# 4001_4153_LO_V2.net
KiCad netlist of a schematic drawn in EAGLE
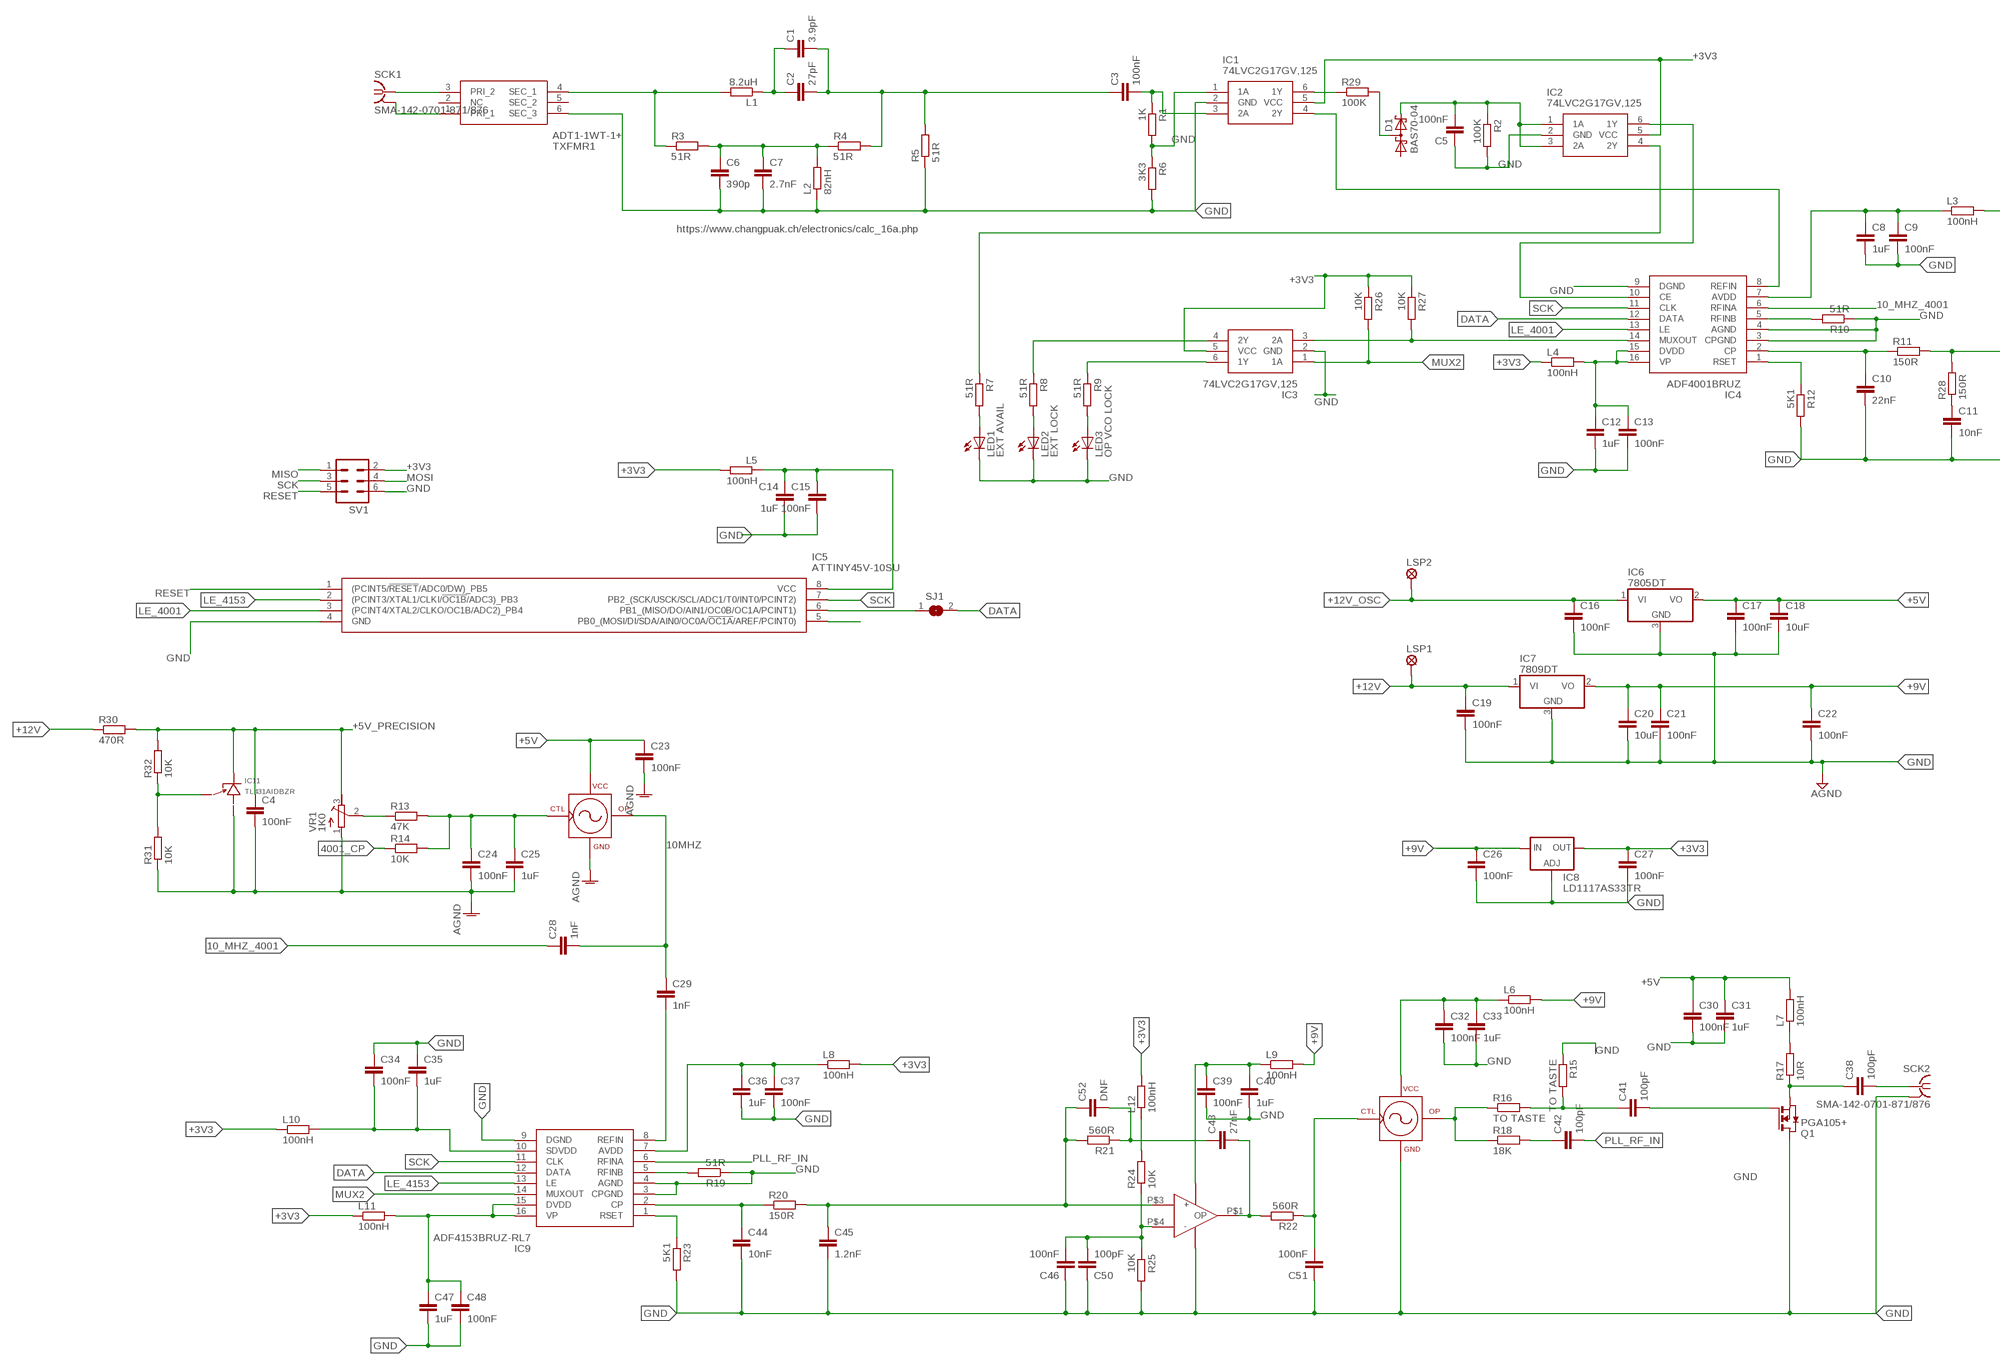
[diagram p0: schematic, sheet 1, part 1 of 2]
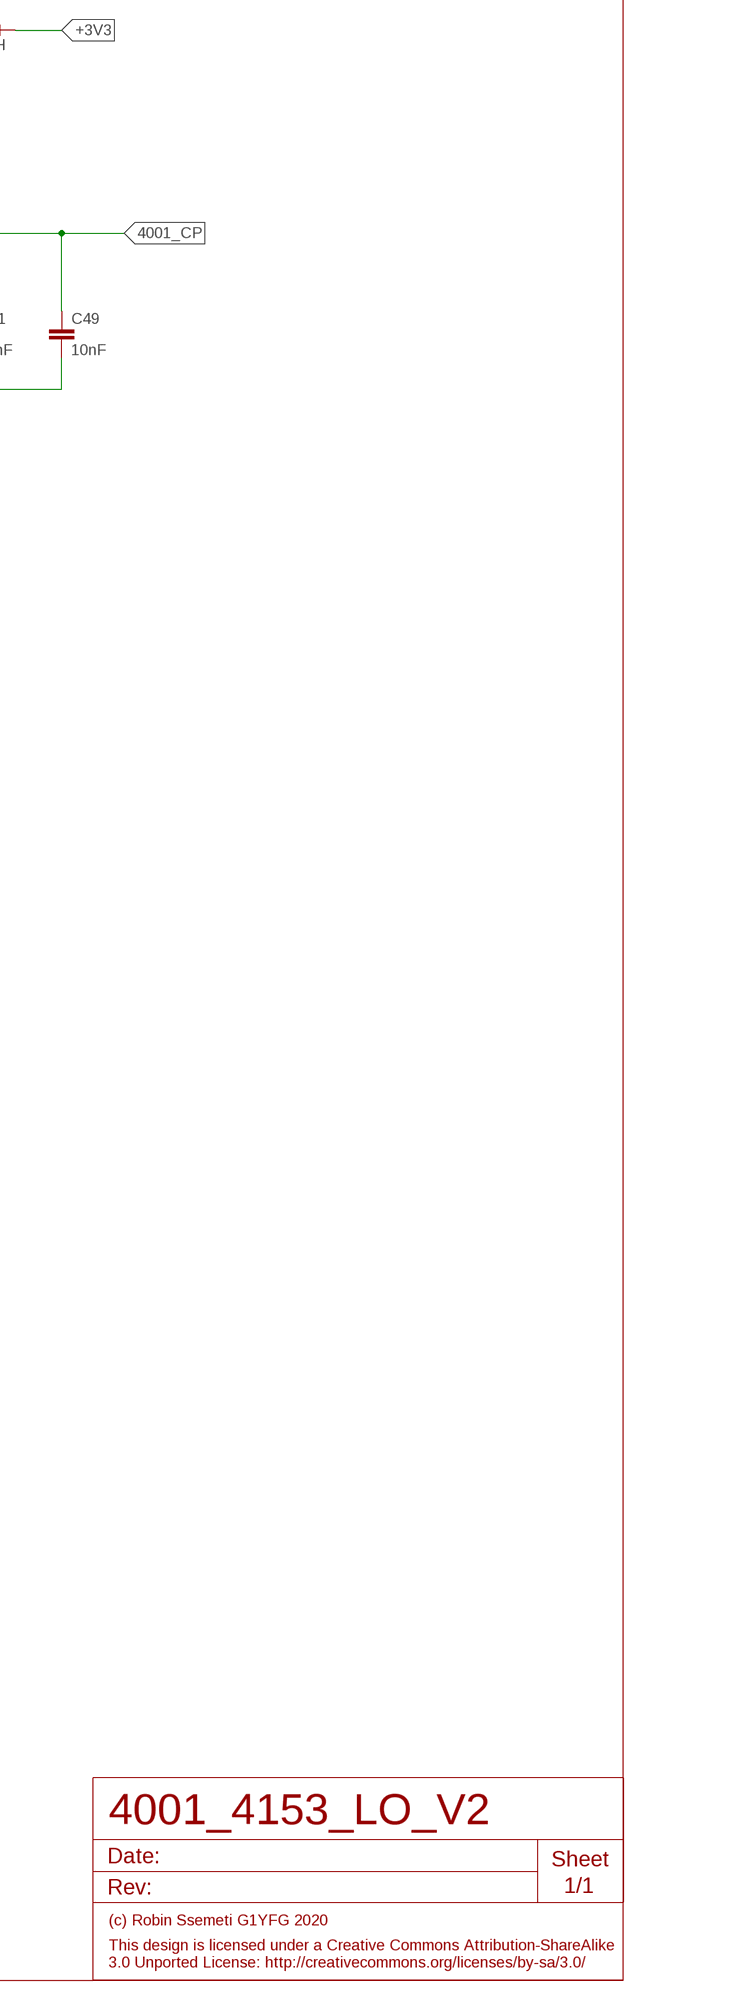
[diagram p1: schematic, sheet 1, part 2 of 2]

(export (version "E")
  (design (tool "Eeschema 10.0.6"))
  (components
    (comp (ref "C1")
      (value "3.9pF")
      (footprint "eagle-import:C0603")
      (libsource (lib "eagle-import") (part "resistor_C-EUC0603"))
    )
    (comp (ref "C2")
      (value "27pF")
      (footprint "eagle-import:C0603")
      (libsource (lib "eagle-import") (part "resistor_C-EUC0603"))
    )
    (comp (ref "C3")
      (value "100nF")
      (footprint "eagle-import:C0603")
      (libsource (lib "eagle-import") (part "resistor_C-EUC0603"))
    )
    (comp (ref "C4")
      (value "100nF")
      (footprint "eagle-import:C0603")
      (libsource (lib "eagle-import") (part "C-EUC0603"))
    )
    (comp (ref "C5")
      (value "100nF")
      (footprint "eagle-import:C0603")
      (libsource (lib "eagle-import") (part "resistor_C-EUC0603"))
    )
    (comp (ref "C6")
      (value "390p")
      (footprint "eagle-import:C0603")
      (libsource (lib "eagle-import") (part "resistor_C-EUC0603"))
    )
    (comp (ref "C7")
      (value "2.7nF")
      (footprint "eagle-import:C0603")
      (libsource (lib "eagle-import") (part "resistor_C-EUC0603"))
    )
    (comp (ref "C8")
      (value "1uF")
      (footprint "eagle-import:C0603")
      (libsource (lib "eagle-import") (part "resistor_C-EUC0603"))
    )
    (comp (ref "C9")
      (value "100nF")
      (footprint "eagle-import:C0603")
      (libsource (lib "eagle-import") (part "resistor_C-EUC0603"))
    )
    (comp (ref "C10")
      (value "22nF")
      (footprint "eagle-import:C0603")
      (libsource (lib "eagle-import") (part "resistor_C-EUC0603"))
    )
    (comp (ref "C11")
      (value "10nF")
      (footprint "eagle-import:C0603")
      (libsource (lib "eagle-import") (part "resistor_C-EUC0603"))
    )
    (comp (ref "C12")
      (value "1uF")
      (footprint "eagle-import:C0603")
      (libsource (lib "eagle-import") (part "resistor_C-EUC0603"))
    )
    (comp (ref "C13")
      (value "100nF")
      (footprint "eagle-import:C0603")
      (libsource (lib "eagle-import") (part "resistor_C-EUC0603"))
    )
    (comp (ref "C14")
      (value "1uF")
      (footprint "eagle-import:C0603")
      (libsource (lib "eagle-import") (part "resistor_C-EUC0603"))
    )
    (comp (ref "C15")
      (value "100nF")
      (footprint "eagle-import:C0603")
      (libsource (lib "eagle-import") (part "resistor_C-EUC0603"))
    )
    (comp (ref "C16")
      (value "100nF")
      (footprint "eagle-import:C0805")
      (libsource (lib "eagle-import") (part "C-EUC0805"))
    )
    (comp (ref "C17")
      (value "100nF")
      (footprint "eagle-import:C0805")
      (libsource (lib "eagle-import") (part "C-EUC0805"))
    )
    (comp (ref "C18")
      (value "10uF")
      (footprint "eagle-import:C0805")
      (libsource (lib "eagle-import") (part "C-EUC0805"))
    )
    (comp (ref "C19")
      (value "100nF")
      (footprint "eagle-import:C0805")
      (libsource (lib "eagle-import") (part "C-EUC0805"))
    )
    (comp (ref "C20")
      (value "10uF")
      (footprint "eagle-import:C0805")
      (libsource (lib "eagle-import") (part "C-EUC0805"))
    )
    (comp (ref "C21")
      (value "100nF")
      (footprint "eagle-import:C0805")
      (libsource (lib "eagle-import") (part "C-EUC0805"))
    )
    (comp (ref "C22")
      (value "100nF")
      (footprint "eagle-import:C0805")
      (libsource (lib "eagle-import") (part "C-EUC0805"))
    )
    (comp (ref "C23")
      (value "100nF")
      (footprint "eagle-import:C0603")
      (libsource (lib "eagle-import") (part "C-EUC0603"))
    )
    (comp (ref "C24")
      (value "100nF")
      (footprint "eagle-import:C0603")
      (libsource (lib "eagle-import") (part "C-EUC0603"))
    )
    (comp (ref "C25")
      (value "1uF")
      (footprint "eagle-import:C0603")
      (libsource (lib "eagle-import") (part "C-EUC0603"))
    )
    (comp (ref "C26")
      (value "100nF")
      (footprint "eagle-import:C0805")
      (libsource (lib "eagle-import") (part "C-EUC0805"))
    )
    (comp (ref "C27")
      (value "100nF")
      (footprint "eagle-import:C0805")
      (libsource (lib "eagle-import") (part "C-EUC0805"))
    )
    (comp (ref "C28")
      (value "1nF")
      (footprint "eagle-import:C0603")
      (libsource (lib "eagle-import") (part "resistor_C-EUC0603"))
    )
    (comp (ref "C29")
      (value "1nF")
      (footprint "eagle-import:C0603")
      (libsource (lib "eagle-import") (part "resistor_C-EUC0603"))
    )
    (comp (ref "C30")
      (value "100nF")
      (footprint "eagle-import:C0603")
      (libsource (lib "eagle-import") (part "resistor_C-EUC0603"))
    )
    (comp (ref "C31")
      (value "1uF")
      (footprint "eagle-import:C0603")
      (libsource (lib "eagle-import") (part "resistor_C-EUC0603"))
    )
    (comp (ref "C32")
      (value "100nF")
      (footprint "eagle-import:C0603")
      (libsource (lib "eagle-import") (part "resistor_C-EUC0603"))
    )
    (comp (ref "C33")
      (value "1uF")
      (footprint "eagle-import:C0603")
      (libsource (lib "eagle-import") (part "resistor_C-EUC0603"))
    )
    (comp (ref "C34")
      (value "100nF")
      (footprint "eagle-import:C0603")
      (libsource (lib "eagle-import") (part "resistor_C-EUC0603"))
    )
    (comp (ref "C35")
      (value "1uF")
      (footprint "eagle-import:C0603")
      (libsource (lib "eagle-import") (part "resistor_C-EUC0603"))
    )
    (comp (ref "C36")
      (value "1uF")
      (footprint "eagle-import:C0603")
      (libsource (lib "eagle-import") (part "resistor_C-EUC0603"))
    )
    (comp (ref "C37")
      (value "100nF")
      (footprint "eagle-import:C0603")
      (libsource (lib "eagle-import") (part "resistor_C-EUC0603"))
    )
    (comp (ref "C38")
      (value "100pF")
      (footprint "eagle-import:C0603")
      (libsource (lib "eagle-import") (part "resistor_C-EUC0603"))
    )
    (comp (ref "C39")
      (value "100nF")
      (footprint "eagle-import:C0603")
      (libsource (lib "eagle-import") (part "resistor_C-EUC0603"))
    )
    (comp (ref "C40")
      (value "1uF")
      (footprint "eagle-import:C0603")
      (libsource (lib "eagle-import") (part "resistor_C-EUC0603"))
    )
    (comp (ref "C41")
      (value "100pF")
      (footprint "eagle-import:C0603")
      (libsource (lib "eagle-import") (part "resistor_C-EUC0603"))
    )
    (comp (ref "C42")
      (value "100pF")
      (footprint "eagle-import:C0603")
      (libsource (lib "eagle-import") (part "resistor_C-EUC0603"))
    )
    (comp (ref "C43")
      (value "27nF")
      (footprint "eagle-import:C0603")
      (libsource (lib "eagle-import") (part "resistor_C-EUC0603"))
    )
    (comp (ref "C44")
      (value "10nF")
      (footprint "eagle-import:C0603")
      (libsource (lib "eagle-import") (part "resistor_C-EUC0603"))
    )
    (comp (ref "C45")
      (value "1.2nF")
      (footprint "eagle-import:C0603")
      (libsource (lib "eagle-import") (part "resistor_C-EUC0603"))
    )
    (comp (ref "C46")
      (value "100nF")
      (footprint "eagle-import:C0603")
      (libsource (lib "eagle-import") (part "resistor_C-EUC0603"))
    )
    (comp (ref "C47")
      (value "1uF")
      (footprint "eagle-import:C0603")
      (libsource (lib "eagle-import") (part "resistor_C-EUC0603"))
    )
    (comp (ref "C48")
      (value "100nF")
      (footprint "eagle-import:C0603")
      (libsource (lib "eagle-import") (part "resistor_C-EUC0603"))
    )
    (comp (ref "C49")
      (value "10nF")
      (footprint "eagle-import:C0603")
      (libsource (lib "eagle-import") (part "resistor_C-EUC0603"))
    )
    (comp (ref "C50")
      (value "100pF")
      (footprint "eagle-import:C0603")
      (libsource (lib "eagle-import") (part "resistor_C-EUC0603"))
    )
    (comp (ref "C51")
      (value "100nF")
      (footprint "eagle-import:C0603")
      (libsource (lib "eagle-import") (part "resistor_C-EUC0603"))
    )
    (comp (ref "C52")
      (value "DNF")
      (footprint "eagle-import:C0603")
      (libsource (lib "eagle-import") (part "resistor_C-EUC0603"))
    )
    (comp (ref "D1")
      (value "BAS70-04")
      (footprint "eagle-import:SOT23")
      (libsource (lib "eagle-import") (part "BAS70-04"))
    )
    (comp (ref "IC1")
      (value "74LVC2G17GV,125")
      (footprint "eagle-import:SOT95P275X110-6N")
      (fields (field (name "MOUSER_PART_NUMBER") "771-74LVC2G17GV-G"))
      (libsource (lib "eagle-import") (part "74LVC2G17GV,125"))
    )
    (comp (ref "IC2")
      (value "74LVC2G17GV,125")
      (footprint "eagle-import:SOT95P275X110-6N")
      (description "74LVC2G17 - Dual non-inverting Schmitt trigger with 5 V tolerant input@en-us")
      (fields
        (field (name "MOUSER_PART_NUMBER") "771-74LVC2G17GV-G")
        (field (name "ARROW_PART_NUMBER") "74LVC2G17GV,125")
        (field (name "ARROW_PRICE-STOCK") "https://www.arrow.com/en/products/74lvc2g17gv125/nexperia?region=nac")
        (field (name "HEIGHT") "1.1mm")
        (field (name "MANUFACTURER_NAME") "Nexperia")
        (field (name "MANUFACTURER_PART_NUMBER") "74LVC2G17GV,125")
        (field (name "MOUSER_PART_NUMBER_1") "771-74LVC2G17GV-G")
        (field (name "MOUSER_PRICE-STOCK") "https://www.mouser.co.uk/ProductDetail/Nexperia/74LVC2G17GV125?qs=me8TqzrmIYV0s3Bq3xwtOg%3D%3D")
      )
      (libsource (lib "eagle-import") (part "74LVC2G17GV,125"))
    )
    (comp (ref "IC3")
      (value "74LVC2G17GV,125")
      (footprint "eagle-import:SOT95P275X110-6N")
      (description "74LVC2G17 - Dual non-inverting Schmitt trigger with 5 V tolerant input@en-us")
      (fields
        (field (name "MOUSER_PART_NUMBER") "771-74LVC2G17GV-G")
        (field (name "ARROW_PART_NUMBER") "74LVC2G17GV,125")
        (field (name "ARROW_PRICE-STOCK") "https://www.arrow.com/en/products/74lvc2g17gv125/nexperia?region=nac")
        (field (name "HEIGHT") "1.1mm")
        (field (name "MANUFACTURER_NAME") "Nexperia")
        (field (name "MANUFACTURER_PART_NUMBER") "74LVC2G17GV,125")
        (field (name "MOUSER_PART_NUMBER_1") "771-74LVC2G17GV-G")
        (field (name "MOUSER_PRICE-STOCK") "https://www.mouser.co.uk/ProductDetail/Nexperia/74LVC2G17GV125?qs=me8TqzrmIYV0s3Bq3xwtOg%3D%3D")
      )
      (libsource (lib "eagle-import") (part "74LVC2G17GV,125"))
    )
    (comp (ref "IC4")
      (value "ADF4001BRUZ")
      (footprint "eagle-import:SOP65P640X120-16N")
      (fields (field (name "MOUSER_PART_NUMBER") "584-ADF4001BRUZ"))
      (libsource (lib "eagle-import") (part "ADF4001BRUZ"))
    )
    (comp (ref "IC5")
      (value "ATTINY45V-10SU")
      (footprint "eagle-import:SOIC127P798X216-8N")
      (fields (field (name "MOUSER_PART_NUMBER") "556-ATTINY45V10SU"))
      (libsource (lib "eagle-import") (part "ATTINY45V-10SU"))
    )
    (comp (ref "IC6")
      (value "7805DT")
      (footprint "eagle-import:TO252")
      (libsource (lib "eagle-import") (part "78DT05"))
    )
    (comp (ref "IC7")
      (value "7809DT")
      (footprint "eagle-import:TO252")
      (libsource (lib "eagle-import") (part "78DT05"))
    )
    (comp (ref "IC8")
      (value "LD1117AS33TR")
      (footprint "eagle-import:SOT223")
      (libsource (lib "eagle-import") (part "LD117A?STR"))
    )
    (comp (ref "IC9")
      (value "ADF4153BRUZ-RL7")
      (footprint "eagle-import:SOP65P640X120-16N")
      (fields (field (name "MOUSER_PART_NUMBER") "584-ADF4153BRUZ-R7"))
      (libsource (lib "eagle-import") (part "ADF4153BRUZ-RL7"))
    )
    (comp (ref "IC10")
      (value "MCP6H01T-E/LT")
      (footprint "eagle-import:SOT23-5")
      (fields (field (name "MPN") "MCP6H01T-E/LT "))
      (libsource (lib "eagle-import") (part "MCP6H01"))
    )
    (comp (ref "IC11")
      (value "TL431AIDBZR")
      (footprint "eagle-import:SOT23L")
      (libsource (lib "eagle-import") (part "TL431AIDBZR"))
    )
    (comp (ref "L1")
      (value "8.2uH")
      (footprint "eagle-import:R0603")
      (libsource (lib "eagle-import") (part "resistor_R-EU_R0603"))
    )
    (comp (ref "L2")
      (value "82nH")
      (footprint "eagle-import:R0603")
      (libsource (lib "eagle-import") (part "resistor_R-EU_R0603"))
    )
    (comp (ref "L3")
      (value "100nH")
      (footprint "eagle-import:R0603")
      (libsource (lib "eagle-import") (part "resistor_R-EU_R0603"))
    )
    (comp (ref "L4")
      (value "100nH")
      (footprint "eagle-import:R0603")
      (libsource (lib "eagle-import") (part "resistor_R-EU_R0603"))
    )
    (comp (ref "L5")
      (value "100nH")
      (footprint "eagle-import:R0603")
      (libsource (lib "eagle-import") (part "resistor_R-EU_R0603"))
    )
    (comp (ref "L6")
      (value "100nH")
      (footprint "eagle-import:R0603")
      (libsource (lib "eagle-import") (part "resistor_R-EU_R0603"))
    )
    (comp (ref "L7")
      (value "100nH")
      (footprint "eagle-import:R0603")
      (libsource (lib "eagle-import") (part "resistor_R-EU_R0603"))
    )
    (comp (ref "L8")
      (value "100nH")
      (footprint "eagle-import:R0603")
      (libsource (lib "eagle-import") (part "resistor_R-EU_R0603"))
    )
    (comp (ref "L9")
      (value "100nH")
      (footprint "eagle-import:R0603")
      (libsource (lib "eagle-import") (part "resistor_R-EU_R0603"))
    )
    (comp (ref "L10")
      (value "100nH")
      (footprint "eagle-import:R0603")
      (libsource (lib "eagle-import") (part "resistor_R-EU_R0603"))
    )
    (comp (ref "L11")
      (value "100nH")
      (footprint "eagle-import:R0603")
      (libsource (lib "eagle-import") (part "resistor_R-EU_R0603"))
    )
    (comp (ref "L12")
      (value "100nH")
      (footprint "eagle-import:R0603")
      (libsource (lib "eagle-import") (part "resistor_R-EU_R0603"))
    )
    (comp (ref "LED1")
      (value "EXT AVAIL")
      (footprint "eagle-import:LED3MM")
      (libsource (lib "eagle-import") (part "LED3MM"))
    )
    (comp (ref "LED2")
      (value "EXT LOCK")
      (footprint "eagle-import:LED3MM")
      (libsource (lib "eagle-import") (part "LED3MM"))
    )
    (comp (ref "LED3")
      (value "OP VCO LOCK")
      (footprint "eagle-import:LED3MM")
      (libsource (lib "eagle-import") (part "LED3MM"))
    )
    (comp (ref "LSP1")
      (value "LSP13")
      (footprint "eagle-import:LSP13")
      (libsource (lib "eagle-import") (part "LSP13"))
    )
    (comp (ref "LSP2")
      (value "LSP13")
      (footprint "eagle-import:LSP13")
      (libsource (lib "eagle-import") (part "LSP13"))
    )
    (comp (ref "OSC1")
      (value "CTI_OSC")
      (footprint "eagle-import:CTI_OSC")
      (libsource (lib "eagle-import") (part "CTI_OSC"))
    )
    (comp (ref "OSC2")
      (value "CRSYTELEK_127")
      (footprint "eagle-import:CRYSTEK_VCO")
      (libsource (lib "eagle-import") (part "CRSYTELEK_127"))
    )
    (comp (ref "Q1")
      (value "PGA105+")
      (footprint "eagle-import:SOT89")
      (libsource (lib "eagle-import") (part "NMOSSOT89"))
    )
    (comp (ref "R1")
      (value "1K")
      (footprint "eagle-import:R0603")
      (libsource (lib "eagle-import") (part "R-EU_R0603"))
    )
    (comp (ref "R2")
      (value "100K")
      (footprint "eagle-import:R0603")
      (libsource (lib "eagle-import") (part "R-EU_R0603"))
    )
    (comp (ref "R3")
      (value "51R")
      (footprint "eagle-import:R0603")
      (libsource (lib "eagle-import") (part "R-EU_R0603"))
    )
    (comp (ref "R4")
      (value "51R")
      (footprint "eagle-import:R0603")
      (libsource (lib "eagle-import") (part "R-EU_R0603"))
    )
    (comp (ref "R5")
      (value "51R")
      (footprint "eagle-import:R0603")
      (libsource (lib "eagle-import") (part "R-EU_R0603"))
    )
    (comp (ref "R6")
      (value "3K3")
      (footprint "eagle-import:R0603")
      (libsource (lib "eagle-import") (part "R-EU_R0603"))
    )
    (comp (ref "R7")
      (value "51R")
      (footprint "eagle-import:R0603")
      (libsource (lib "eagle-import") (part "R-EU_R0603"))
    )
    (comp (ref "R8")
      (value "51R")
      (footprint "eagle-import:R0603")
      (libsource (lib "eagle-import") (part "R-EU_R0603"))
    )
    (comp (ref "R9")
      (value "51R")
      (footprint "eagle-import:R0603")
      (libsource (lib "eagle-import") (part "R-EU_R0603"))
    )
    (comp (ref "R10")
      (value "51R")
      (footprint "eagle-import:R0603")
      (libsource (lib "eagle-import") (part "R-EU_R0603"))
    )
    (comp (ref "R11")
      (value "150R")
      (footprint "eagle-import:R0603")
      (libsource (lib "eagle-import") (part "R-EU_R0603"))
    )
    (comp (ref "R12")
      (value "5K1")
      (footprint "eagle-import:R0603")
      (libsource (lib "eagle-import") (part "R-EU_R0603"))
    )
    (comp (ref "R13")
      (value "47K")
      (footprint "eagle-import:R0603")
      (libsource (lib "eagle-import") (part "R-EU_R0603"))
    )
    (comp (ref "R14")
      (value "10K")
      (footprint "eagle-import:R0603")
      (libsource (lib "eagle-import") (part "R-EU_R0603"))
    )
    (comp (ref "R15")
      (value "TO TASTE")
      (footprint "eagle-import:R0603")
      (libsource (lib "eagle-import") (part "R-EU_R0603"))
    )
    (comp (ref "R16")
      (value "TO TASTE")
      (footprint "eagle-import:R0603")
      (libsource (lib "eagle-import") (part "R-EU_R0603"))
    )
    (comp (ref "R17")
      (value "10R")
      (footprint "eagle-import:R0603")
      (libsource (lib "eagle-import") (part "R-EU_R0603"))
    )
    (comp (ref "R18")
      (value "18K")
      (footprint "eagle-import:R0603")
      (libsource (lib "eagle-import") (part "R-EU_R0603"))
    )
    (comp (ref "R19")
      (value "51R")
      (footprint "eagle-import:R0603")
      (libsource (lib "eagle-import") (part "R-EU_R0603"))
    )
    (comp (ref "R20")
      (value "150R")
      (footprint "eagle-import:R0603")
      (libsource (lib "eagle-import") (part "R-EU_R0603"))
    )
    (comp (ref "R21")
      (value "560R")
      (footprint "eagle-import:R0603")
      (libsource (lib "eagle-import") (part "R-EU_R0603"))
    )
    (comp (ref "R22")
      (value "560R")
      (footprint "eagle-import:R0603")
      (libsource (lib "eagle-import") (part "R-EU_R0603"))
    )
    (comp (ref "R23")
      (value "5K1")
      (footprint "eagle-import:R0603")
      (libsource (lib "eagle-import") (part "R-EU_R0603"))
    )
    (comp (ref "R24")
      (value "10K")
      (footprint "eagle-import:R0603")
      (libsource (lib "eagle-import") (part "R-EU_R0603"))
    )
    (comp (ref "R25")
      (value "10K")
      (footprint "eagle-import:R0603")
      (libsource (lib "eagle-import") (part "R-EU_R0603"))
    )
    (comp (ref "R26")
      (value "10K")
      (footprint "eagle-import:R0603")
      (libsource (lib "eagle-import") (part "R-EU_R0603"))
    )
    (comp (ref "R27")
      (value "10K")
      (footprint "eagle-import:R0603")
      (libsource (lib "eagle-import") (part "R-EU_R0603"))
    )
    (comp (ref "R28")
      (value "150R")
      (footprint "eagle-import:R0603")
      (libsource (lib "eagle-import") (part "R-EU_R0603"))
    )
    (comp (ref "R29")
      (value "100K")
      (footprint "eagle-import:R0603")
      (libsource (lib "eagle-import") (part "R-EU_R0603"))
    )
    (comp (ref "R30")
      (value "470R")
      (footprint "eagle-import:R0603")
      (libsource (lib "eagle-import") (part "R-EU_R0603"))
    )
    (comp (ref "R31")
      (value "10K")
      (footprint "eagle-import:R0603")
      (libsource (lib "eagle-import") (part "R-EU_R0603"))
    )
    (comp (ref "R32")
      (value "10K")
      (footprint "eagle-import:R0603")
      (libsource (lib "eagle-import") (part "R-EU_R0603"))
    )
    (comp (ref "SCK1")
      (value "SMA-142-0701-871/876")
      (footprint "eagle-import:J502-ND-142-0701-871_876")
      (fields (field (name "MF") "JOHNSON COMPONENTS") (field (name "MPN") "142-0701-871"))
      (libsource (lib "eagle-import") (part "SMA-142-0701-871/876"))
    )
    (comp (ref "SCK2")
      (value "SMA-142-0701-871/876")
      (footprint "eagle-import:J502-ND-142-0701-871_876")
      (fields
        (field (name "MF") "JOHNSON COMPONENTS")
        (field (name "MPN") "142-0701-871")
        (field (name "MF_1") "JOHNSON COMPONENTS")
        (field (name "MPN_1") "142-0701-871")
        (field (name "OC_FARNELL") "1339835")
        (field (name "OC_NEWARK") "91B6105")
      )
      (libsource (lib "eagle-import") (part "SMA-142-0701-871/876"))
    )
    (comp (ref "SJ1") (value "SJ") (footprint "eagle-import:SJ") (libsource (lib "eagle-import") (part "SJ")))
    (comp (ref "SV1")
      (value "ML6")
      (footprint "eagle-import:ML6")
      (fields (field (name "MPN") "MC-254-06-00-ST-DIP ") (field (name "OC_FARNELL") "2843525"))
      (libsource (lib "eagle-import") (part "ML6"))
    )
    (comp (ref "TXFMR1")
      (value "ADT1-1WT-1+")
      (footprint "eagle-import:SOP254P691X284-6N")
      (fields (field (name "MOUSER_PART_NUMBER") "139-ADT1-1WT-1"))
      (libsource (lib "eagle-import") (part "ADT1-1WT-1+"))
    )
    (comp (ref "VR1")
      (value "1K0")
      (footprint "eagle-import:RTRIM64Y")
      (fields (field (name "MPN") "3296Y-1-103LF "))
      (libsource (lib "eagle-import") (part "R-TRIMM64Y"))
    )
  )
  (nets
    (net (code "1") (name "+3V3") (class "Default")
      (node (ref "C27") (pin "1") (pinfunction "1_1") (pintype "passive"))
      (node (ref "IC1") (pin "5") (pinfunction "VCC_5") (pintype "bidirectional"))
      (node (ref "IC2") (pin "5") (pinfunction "VCC_5") (pintype "bidirectional"))
      (node (ref "IC3") (pin "5") (pinfunction "VCC_5") (pintype "bidirectional"))
      (node (ref "IC8") (pin "4") (pinfunction "OUT_4") (pintype "passive"))
      (node (ref "L10") (pin "1") (pinfunction "1_1") (pintype "passive"))
      (node (ref "L11") (pin "1") (pinfunction "1_1") (pintype "passive"))
      (node (ref "L12") (pin "2") (pinfunction "2_2") (pintype "passive"))
      (node (ref "L3") (pin "2") (pinfunction "2_2") (pintype "passive"))
      (node (ref "L4") (pin "1") (pinfunction "1_1") (pintype "passive"))
      (node (ref "L5") (pin "2") (pinfunction "2_2") (pintype "passive"))
      (node (ref "L8") (pin "2") (pinfunction "2_2") (pintype "passive"))
      (node (ref "R26") (pin "1") (pinfunction "1_1") (pintype "passive"))
      (node (ref "R27") (pin "1") (pinfunction "1_1") (pintype "passive"))
      (node (ref "SV1") (pin "2") (pinfunction "2_2") (pintype "passive"))
    )
    (net (code "2") (name "+5V") (class "Default")
      (node (ref "C17") (pin "1") (pinfunction "1_1") (pintype "passive"))
      (node (ref "C18") (pin "1") (pinfunction "1_1") (pintype "passive"))
      (node (ref "C23") (pin "1") (pinfunction "1_1") (pintype "passive"))
      (node (ref "C30") (pin "1") (pinfunction "1_1") (pintype "passive"))
      (node (ref "C31") (pin "1") (pinfunction "1_1") (pintype "passive"))
      (node (ref "IC6") (pin "2") (pinfunction "VO_2") (pintype "passive"))
      (node (ref "L7") (pin "2") (pinfunction "2_2") (pintype "passive"))
      (node (ref "OSC1") (pin "VCC") (pinfunction "VCC_VCC") (pintype "bidirectional"))
    )
    (net (code "3") (name "+9V") (class "Default")
      (node (ref "C20") (pin "1") (pinfunction "1_1") (pintype "passive"))
      (node (ref "C21") (pin "1") (pinfunction "1_1") (pintype "passive"))
      (node (ref "C22") (pin "1") (pinfunction "1_1") (pintype "passive"))
      (node (ref "C26") (pin "1") (pinfunction "1_1") (pintype "passive"))
      (node (ref "IC7") (pin "2") (pinfunction "VO_2") (pintype "passive"))
      (node (ref "IC8") (pin "3") (pinfunction "IN_3") (pintype "input"))
      (node (ref "L6") (pin "2") (pinfunction "2_2") (pintype "passive"))
      (node (ref "L9") (pin "2") (pinfunction "2_2") (pintype "passive"))
    )
    (net (code "4") (name "+12V") (class "Default")
      (node (ref "C19") (pin "1") (pinfunction "1_1") (pintype "passive"))
      (node (ref "IC7") (pin "1") (pinfunction "VI_1") (pintype "input"))
      (node (ref "LSP1") (pin "MP") (pinfunction "MP_MP") (pintype "passive"))
      (node (ref "R30") (pin "1") (pinfunction "1_1") (pintype "passive"))
    )
    (net (code "5") (name "+12V_OSC") (class "Default")
      (node (ref "C16") (pin "1") (pinfunction "1_1") (pintype "passive"))
      (node (ref "IC6") (pin "1") (pinfunction "VI_1") (pintype "input"))
      (node (ref "LSP2") (pin "MP") (pinfunction "MP_MP") (pintype "passive"))
    )
    (net (code "6") (name "/+5V_PRECISION") (class "Default")
      (node (ref "C4") (pin "1") (pinfunction "1_1") (pintype "passive"))
      (node (ref "IC11") (pin "G") (pinfunction "CATHODE_G") (pintype "bidirectional"))
      (node (ref "R30") (pin "2") (pinfunction "2_2") (pintype "passive"))
      (node (ref "R32") (pin "2") (pinfunction "2_2") (pintype "passive"))
      (node (ref "VR1") (pin "3") (pinfunction "A_3") (pintype "passive"))
    )
    (net (code "7") (name "/10MHZ") (class "Default")
      (node (ref "C28") (pin "2") (pinfunction "2_2") (pintype "passive"))
      (node (ref "C29") (pin "1") (pinfunction "1_1") (pintype "passive"))
      (node (ref "OSC1") (pin "OUT") (pinfunction "OP_OUT") (pintype "bidirectional"))
    )
    (net (code "8") (name "/MISO") (class "Default")
      (node (ref "IC5") (pin "6") (pinfunction "PB1_(MISO/DO/AIN1/OC0B/OC1A/PCINT1)_6") (pintype "bidirectional"))
      (node (ref "SJ1") (pin "1") (pinfunction "1_1") (pintype "passive"))
      (node (ref "SV1") (pin "1") (pinfunction "1_1") (pintype "passive"))
    )
    (net (code "9") (name "/MOSI") (class "Default")
      (node (ref "IC5") (pin "5") (pinfunction "PB0_(MOSI/DI/SDA/AIN0/OC0A/~{OC1A}/AREF/PCINT0)_5") (pintype "bidirectional"))
      (node (ref "SV1") (pin "4") (pinfunction "4_4") (pintype "passive"))
    )
    (net (code "10") (name "/RESET") (class "Default")
      (node (ref "IC5") (pin "1") (pinfunction "(PCINT5/~{RESET}/ADC0/DW)_PB5_1") (pintype "bidirectional"))
      (node (ref "SV1") (pin "5") (pinfunction "5_5") (pintype "passive"))
    )
    (net (code "11") (name "10_MHZ_4001") (class "Default")
      (node (ref "C28") (pin "1") (pinfunction "1_1") (pintype "passive"))
      (node (ref "IC4") (pin "6") (pinfunction "RFINA_6") (pintype "bidirectional"))
    )
    (net (code "12") (name "4001_CP") (class "Default")
      (node (ref "C49") (pin "1") (pinfunction "1_1") (pintype "passive"))
      (node (ref "R11") (pin "2") (pinfunction "2_2") (pintype "passive"))
      (node (ref "R14") (pin "1") (pinfunction "1_1") (pintype "passive"))
      (node (ref "R28") (pin "2") (pinfunction "2_2") (pintype "passive"))
    )
    (net (code "13") (name "DATA") (class "Default")
      (node (ref "IC4") (pin "12") (pinfunction "DATA_12") (pintype "bidirectional"))
      (node (ref "IC9") (pin "12") (pinfunction "DATA_12") (pintype "bidirectional"))
      (node (ref "SJ1") (pin "2") (pinfunction "2_2") (pintype "passive"))
    )
    (net (code "14") (name "GND") (class "Default")
      (node (ref "C10") (pin "2") (pinfunction "2_2") (pintype "passive"))
      (node (ref "C11") (pin "2") (pinfunction "2_2") (pintype "passive"))
      (node (ref "C12") (pin "2") (pinfunction "2_2") (pintype "passive"))
      (node (ref "C13") (pin "2") (pinfunction "2_2") (pintype "passive"))
      (node (ref "C14") (pin "2") (pinfunction "2_2") (pintype "passive"))
      (node (ref "C15") (pin "2") (pinfunction "2_2") (pintype "passive"))
      (node (ref "C16") (pin "2") (pinfunction "2_2") (pintype "passive"))
      (node (ref "C17") (pin "2") (pinfunction "2_2") (pintype "passive"))
      (node (ref "C18") (pin "2") (pinfunction "2_2") (pintype "passive"))
      (node (ref "C19") (pin "2") (pinfunction "2_2") (pintype "passive"))
      (node (ref "C20") (pin "2") (pinfunction "2_2") (pintype "passive"))
      (node (ref "C21") (pin "2") (pinfunction "2_2") (pintype "passive"))
      (node (ref "C22") (pin "2") (pinfunction "2_2") (pintype "passive"))
      (node (ref "C23") (pin "2") (pinfunction "2_2") (pintype "passive"))
      (node (ref "C24") (pin "2") (pinfunction "2_2") (pintype "passive"))
      (node (ref "C25") (pin "2") (pinfunction "2_2") (pintype "passive"))
      (node (ref "C26") (pin "2") (pinfunction "2_2") (pintype "passive"))
      (node (ref "C27") (pin "2") (pinfunction "2_2") (pintype "passive"))
      (node (ref "C30") (pin "2") (pinfunction "2_2") (pintype "passive"))
      (node (ref "C31") (pin "2") (pinfunction "2_2") (pintype "passive"))
      (node (ref "C32") (pin "2") (pinfunction "2_2") (pintype "passive"))
      (node (ref "C33") (pin "2") (pinfunction "2_2") (pintype "passive"))
      (node (ref "C34") (pin "1") (pinfunction "1_1") (pintype "passive"))
      (node (ref "C35") (pin "1") (pinfunction "1_1") (pintype "passive"))
      (node (ref "C36") (pin "2") (pinfunction "2_2") (pintype "passive"))
      (node (ref "C37") (pin "2") (pinfunction "2_2") (pintype "passive"))
      (node (ref "C39") (pin "2") (pinfunction "2_2") (pintype "passive"))
      (node (ref "C4") (pin "2") (pinfunction "2_2") (pintype "passive"))
      (node (ref "C40") (pin "2") (pinfunction "2_2") (pintype "passive"))
      (node (ref "C44") (pin "2") (pinfunction "2_2") (pintype "passive"))
      (node (ref "C45") (pin "2") (pinfunction "2_2") (pintype "passive"))
      (node (ref "C46") (pin "1") (pinfunction "1_1") (pintype "passive"))
      (node (ref "C47") (pin "2") (pinfunction "2_2") (pintype "passive"))
      (node (ref "C48") (pin "2") (pinfunction "2_2") (pintype "passive"))
      (node (ref "C49") (pin "2") (pinfunction "2_2") (pintype "passive"))
      (node (ref "C5") (pin "1") (pinfunction "1_1") (pintype "passive"))
      (node (ref "C50") (pin "1") (pinfunction "1_1") (pintype "passive"))
      (node (ref "C51") (pin "1") (pinfunction "1_1") (pintype "passive"))
      (node (ref "C6") (pin "2") (pinfunction "2_2") (pintype "passive"))
      (node (ref "C7") (pin "2") (pinfunction "2_2") (pintype "passive"))
      (node (ref "C8") (pin "2") (pinfunction "2_2") (pintype "passive"))
      (node (ref "C9") (pin "2") (pinfunction "2_2") (pintype "passive"))
      (node (ref "IC1") (pin "2") (pinfunction "GND_2") (pintype "bidirectional"))
      (node (ref "IC10") (pin "P$2") (pinfunction "-VE_P$2") (pintype "bidirectional"))
      (node (ref "IC11") (pin "D") (pinfunction "ANODE_D") (pintype "bidirectional"))
      (node (ref "IC2") (pin "2") (pinfunction "GND_2") (pintype "bidirectional"))
      (node (ref "IC3") (pin "2") (pinfunction "GND_2") (pintype "bidirectional"))
      (node (ref "IC4") (pin "3") (pinfunction "CPGND_3") (pintype "bidirectional"))
      (node (ref "IC4") (pin "4") (pinfunction "AGND_4") (pintype "bidirectional"))
      (node (ref "IC4") (pin "9") (pinfunction "DGND_9") (pintype "bidirectional"))
      (node (ref "IC5") (pin "4") (pinfunction "GND_4") (pintype "bidirectional"))
      (node (ref "IC6") (pin "3") (pinfunction "GND_3") (pintype "passive"))
      (node (ref "IC7") (pin "3") (pinfunction "GND_3") (pintype "passive"))
      (node (ref "IC8") (pin "1") (pinfunction "ADJ_1") (pintype "input"))
      (node (ref "IC9") (pin "3") (pinfunction "CPGND_3") (pintype "bidirectional"))
      (node (ref "IC9") (pin "4") (pinfunction "AGND_4") (pintype "bidirectional"))
      (node (ref "IC9") (pin "9") (pinfunction "DGND_9") (pintype "bidirectional"))
      (node (ref "L2") (pin "1") (pinfunction "1_1") (pintype "passive"))
      (node (ref "LED1") (pin "K") (pinfunction "C_K") (pintype "passive"))
      (node (ref "LED2") (pin "K") (pinfunction "C_K") (pintype "passive"))
      (node (ref "LED3") (pin "K") (pinfunction "C_K") (pintype "passive"))
      (node (ref "OSC1") (pin "GND") (pinfunction "GND_GND") (pintype "bidirectional"))
      (node (ref "OSC2") (pin "P$1") (pinfunction "GND_P$1") (pintype "bidirectional"))
      (node (ref "OSC2") (pin "P$11") (pinfunction "GND_P$11") (pintype "bidirectional"))
      (node (ref "OSC2") (pin "P$12") (pinfunction "GND_P$12") (pintype "bidirectional"))
      (node (ref "OSC2") (pin "P$13") (pinfunction "GND_P$13") (pintype "bidirectional"))
      (node (ref "OSC2") (pin "P$15") (pinfunction "GND_P$15") (pintype "bidirectional"))
      (node (ref "OSC2") (pin "P$16") (pinfunction "GND_P$16") (pintype "bidirectional"))
      (node (ref "OSC2") (pin "P$3") (pinfunction "GND_P$3") (pintype "bidirectional"))
      (node (ref "OSC2") (pin "P$4") (pinfunction "GND_P$4") (pintype "bidirectional"))
      (node (ref "OSC2") (pin "P$5") (pinfunction "GND_P$5") (pintype "bidirectional"))
      (node (ref "OSC2") (pin "P$6") (pinfunction "GND_P$6") (pintype "bidirectional"))
      (node (ref "OSC2") (pin "P$7") (pinfunction "GND_P$7") (pintype "bidirectional"))
      (node (ref "OSC2") (pin "P$8") (pinfunction "GND_P$8") (pintype "bidirectional"))
      (node (ref "OSC2") (pin "P$9") (pinfunction "GND_P$9") (pintype "bidirectional"))
      (node (ref "Q1") (pin "2") (pinfunction "D_2") (pintype "passive"))
      (node (ref "R10") (pin "1") (pinfunction "1_1") (pintype "passive"))
      (node (ref "R12") (pin "2") (pinfunction "2_2") (pintype "passive"))
      (node (ref "R15") (pin "1") (pinfunction "1_1") (pintype "passive"))
      (node (ref "R19") (pin "1") (pinfunction "1_1") (pintype "passive"))
      (node (ref "R2") (pin "2") (pinfunction "2_2") (pintype "passive"))
      (node (ref "R23") (pin "2") (pinfunction "2_2") (pintype "passive"))
      (node (ref "R25") (pin "2") (pinfunction "2_2") (pintype "passive"))
      (node (ref "R31") (pin "1") (pinfunction "1_1") (pintype "passive"))
      (node (ref "R5") (pin "1") (pinfunction "1_1") (pintype "passive"))
      (node (ref "R6") (pin "2") (pinfunction "2_2") (pintype "passive"))
      (node (ref "SCK1") (pin "G@1") (pinfunction "GND_G@1") (pintype "power_in"))
      (node (ref "SCK2") (pin "G@1") (pinfunction "GND_G@1") (pintype "power_in"))
      (node (ref "SV1") (pin "6") (pinfunction "6_6") (pintype "passive"))
      (node (ref "TXFMR1") (pin "1") (pinfunction "PRI_1_1") (pintype "bidirectional"))
      (node (ref "TXFMR1") (pin "6") (pinfunction "SEC_3_6") (pintype "bidirectional"))
      (node (ref "VR1") (pin "1") (pinfunction "E_1") (pintype "passive"))
    )
    (net (code "15") (name "LE_4001") (class "Default")
      (node (ref "IC4") (pin "13") (pinfunction "LE_13") (pintype "bidirectional"))
      (node (ref "IC5") (pin "3") (pinfunction "(PCINT4/XTAL2/CLKO/OC1B/ADC2)_PB4_3") (pintype "bidirectional"))
    )
    (net (code "16") (name "LE_4153") (class "Default")
      (node (ref "IC5") (pin "2") (pinfunction "(PCINT3/XTAL1/CLKI/~{OC1B}/ADC3)_PB3_2") (pintype "bidirectional"))
      (node (ref "IC9") (pin "13") (pinfunction "LE_13") (pintype "bidirectional"))
    )
    (net (code "17") (name "MUX2") (class "Default")
      (node (ref "IC3") (pin "1") (pinfunction "1A_1") (pintype "bidirectional"))
      (node (ref "IC9") (pin "14") (pinfunction "MUXOUT_14") (pintype "bidirectional"))
      (node (ref "R26") (pin "2") (pinfunction "2_2") (pintype "passive"))
    )
    (net (code "18") (name "Net-(C1-Pad1)") (class "Default")
      (node (ref "C1") (pin "1") (pinfunction "1_1") (pintype "passive"))
      (node (ref "C2") (pin "1") (pinfunction "1_1") (pintype "passive"))
      (node (ref "L1") (pin "1") (pinfunction "1_1") (pintype "passive"))
    )
    (net (code "19") (name "Net-(C1-Pad2)") (class "Default")
      (node (ref "C1") (pin "2") (pinfunction "2_2") (pintype "passive"))
      (node (ref "C2") (pin "2") (pinfunction "2_2") (pintype "passive"))
      (node (ref "C3") (pin "1") (pinfunction "1_1") (pintype "passive"))
      (node (ref "R4") (pin "2") (pinfunction "2_2") (pintype "passive"))
      (node (ref "R5") (pin "2") (pinfunction "2_2") (pintype "passive"))
    )
    (net (code "20") (name "Net-(C6-Pad1)") (class "Default")
      (node (ref "C6") (pin "1") (pinfunction "1_1") (pintype "passive"))
      (node (ref "C7") (pin "1") (pinfunction "1_1") (pintype "passive"))
      (node (ref "L2") (pin "2") (pinfunction "2_2") (pintype "passive"))
      (node (ref "R3") (pin "2") (pinfunction "2_2") (pintype "passive"))
      (node (ref "R4") (pin "1") (pinfunction "1_1") (pintype "passive"))
    )
    (net (code "21") (name "Net-(C11-Pad1)") (class "Default")
      (node (ref "C11") (pin "1") (pinfunction "1_1") (pintype "passive"))
      (node (ref "R28") (pin "1") (pinfunction "1_1") (pintype "passive"))
    )
    (net (code "22") (name "Net-(C38-Pad2)") (class "Default")
      (node (ref "C38") (pin "2") (pinfunction "2_2") (pintype "passive"))
      (node (ref "SCK2") (pin "1") (pinfunction "1_1") (pintype "passive"))
    )
    (net (code "23") (name "Net-(C41-Pad1)") (class "Default")
      (node (ref "C41") (pin "1") (pinfunction "1_1") (pintype "passive"))
      (node (ref "R15") (pin "2") (pinfunction "2_2") (pintype "passive"))
      (node (ref "R16") (pin "2") (pinfunction "2_2") (pintype "passive"))
    )
    (net (code "24") (name "Net-(C42-Pad1)") (class "Default")
      (node (ref "C42") (pin "1") (pinfunction "1_1") (pintype "passive"))
      (node (ref "R18") (pin "2") (pinfunction "2_2") (pintype "passive"))
    )
    (net (code "25") (name "Net-(C43-Pad1)") (class "Default")
      (node (ref "C43") (pin "1") (pinfunction "1_1") (pintype "passive"))
      (node (ref "C52") (pin "2") (pinfunction "2_2") (pintype "passive"))
      (node (ref "R21") (pin "1") (pinfunction "1_1") (pintype "passive"))
    )
    (net (code "26") (name "Net-(D1-C1A2)") (class "Default")
      (node (ref "D1") (pin "3") (pinfunction "C1A2_3") (pintype "passive"))
      (node (ref "R29") (pin "2") (pinfunction "2_2") (pintype "passive"))
    )
    (net (code "27") (name "Net-(D1-C2)") (class "Default")
      (node (ref "C5") (pin "2") (pinfunction "2_2") (pintype "passive"))
      (node (ref "D1") (pin "2") (pinfunction "C2_2") (pintype "passive"))
      (node (ref "IC2") (pin "1") (pinfunction "1A_1") (pintype "bidirectional"))
      (node (ref "IC2") (pin "3") (pinfunction "2A_3") (pintype "bidirectional"))
      (node (ref "R2") (pin "1") (pinfunction "1_1") (pintype "passive"))
    )
    (net (code "28") (name "Net-(IC1-1A)") (class "Default")
      (node (ref "IC1") (pin "1") (pinfunction "1A_1") (pintype "bidirectional"))
      (node (ref "R1") (pin "2") (pinfunction "2_2") (pintype "passive"))
      (node (ref "R6") (pin "1") (pinfunction "1_1") (pintype "passive"))
    )
    (net (code "29") (name "Net-(IC1-1Y)") (class "Default")
      (node (ref "IC1") (pin "6") (pinfunction "1Y_6") (pintype "bidirectional"))
      (node (ref "R29") (pin "1") (pinfunction "1_1") (pintype "passive"))
    )
    (net (code "30") (name "Net-(IC1-2A)") (class "Default")
      (node (ref "C3") (pin "2") (pinfunction "2_2") (pintype "passive"))
      (node (ref "IC1") (pin "3") (pinfunction "2A_3") (pintype "bidirectional"))
      (node (ref "R1") (pin "1") (pinfunction "1_1") (pintype "passive"))
    )
    (net (code "31") (name "Net-(IC1-2Y)") (class "Default")
      (node (ref "IC1") (pin "4") (pinfunction "2Y_4") (pintype "bidirectional"))
      (node (ref "IC4") (pin "8") (pinfunction "REFIN_8") (pintype "bidirectional"))
    )
    (net (code "32") (name "Net-(IC2-1Y)") (class "Default")
      (node (ref "IC2") (pin "6") (pinfunction "1Y_6") (pintype "bidirectional"))
      (node (ref "IC4") (pin "10") (pinfunction "CE_10") (pintype "bidirectional"))
    )
    (net (code "33") (name "Net-(IC2-2Y)") (class "Default")
      (node (ref "IC2") (pin "4") (pinfunction "2Y_4") (pintype "bidirectional"))
      (node (ref "R7") (pin "1") (pinfunction "1_1") (pintype "passive"))
    )
    (net (code "34") (name "Net-(IC3-1Y)") (class "Default")
      (node (ref "IC3") (pin "6") (pinfunction "1Y_6") (pintype "bidirectional"))
      (node (ref "R9") (pin "1") (pinfunction "1_1") (pintype "passive"))
    )
    (net (code "35") (name "Net-(IC3-2A)") (class "Default")
      (node (ref "IC3") (pin "3") (pinfunction "2A_3") (pintype "bidirectional"))
      (node (ref "IC4") (pin "14") (pinfunction "MUXOUT_14") (pintype "bidirectional"))
      (node (ref "R27") (pin "2") (pinfunction "2_2") (pintype "passive"))
    )
    (net (code "36") (name "Net-(IC3-2Y)") (class "Default")
      (node (ref "IC3") (pin "4") (pinfunction "2Y_4") (pintype "bidirectional"))
      (node (ref "R8") (pin "1") (pinfunction "1_1") (pintype "passive"))
    )
    (net (code "37") (name "Net-(IC4-AVDD)") (class "Default")
      (node (ref "C8") (pin "1") (pinfunction "1_1") (pintype "passive"))
      (node (ref "C9") (pin "1") (pinfunction "1_1") (pintype "passive"))
      (node (ref "IC4") (pin "7") (pinfunction "AVDD_7") (pintype "bidirectional"))
      (node (ref "L3") (pin "1") (pinfunction "1_1") (pintype "passive"))
    )
    (net (code "38") (name "Net-(IC4-CP)") (class "Default")
      (node (ref "C10") (pin "1") (pinfunction "1_1") (pintype "passive"))
      (node (ref "IC4") (pin "2") (pinfunction "CP_2") (pintype "bidirectional"))
      (node (ref "R11") (pin "1") (pinfunction "1_1") (pintype "passive"))
    )
    (net (code "39") (name "Net-(IC4-DVDD)") (class "Default")
      (node (ref "C12") (pin "1") (pinfunction "1_1") (pintype "passive"))
      (node (ref "C13") (pin "1") (pinfunction "1_1") (pintype "passive"))
      (node (ref "IC4") (pin "15") (pinfunction "DVDD_15") (pintype "bidirectional"))
      (node (ref "IC4") (pin "16") (pinfunction "VP_16") (pintype "bidirectional"))
      (node (ref "L4") (pin "2") (pinfunction "2_2") (pintype "passive"))
    )
    (net (code "40") (name "Net-(IC4-RFINB)") (class "Default")
      (node (ref "IC4") (pin "5") (pinfunction "RFINB_5") (pintype "bidirectional"))
      (node (ref "R10") (pin "2") (pinfunction "2_2") (pintype "passive"))
    )
    (net (code "41") (name "Net-(IC4-RSET)") (class "Default")
      (node (ref "IC4") (pin "1") (pinfunction "RSET_1") (pintype "bidirectional"))
      (node (ref "R12") (pin "1") (pinfunction "1_1") (pintype "passive"))
    )
    (net (code "42") (name "Net-(IC5-VCC)") (class "Default")
      (node (ref "C14") (pin "1") (pinfunction "1_1") (pintype "passive"))
      (node (ref "C15") (pin "1") (pinfunction "1_1") (pintype "passive"))
      (node (ref "IC5") (pin "8") (pinfunction "VCC_8") (pintype "bidirectional"))
      (node (ref "L5") (pin "1") (pinfunction "1_1") (pintype "passive"))
    )
    (net (code "43") (name "Net-(IC9-AVDD)") (class "Default")
      (node (ref "C36") (pin "1") (pinfunction "1_1") (pintype "passive"))
      (node (ref "C37") (pin "1") (pinfunction "1_1") (pintype "passive"))
      (node (ref "IC9") (pin "7") (pinfunction "AVDD_7") (pintype "bidirectional"))
      (node (ref "L8") (pin "1") (pinfunction "1_1") (pintype "passive"))
    )
    (net (code "44") (name "Net-(IC9-CP)") (class "Default")
      (node (ref "C44") (pin "1") (pinfunction "1_1") (pintype "passive"))
      (node (ref "IC9") (pin "2") (pinfunction "CP_2") (pintype "bidirectional"))
      (node (ref "R20") (pin "1") (pinfunction "1_1") (pintype "passive"))
    )
    (net (code "45") (name "Net-(IC9-DVDD)") (class "Default")
      (node (ref "C47") (pin "1") (pinfunction "1_1") (pintype "passive"))
      (node (ref "C48") (pin "1") (pinfunction "1_1") (pintype "passive"))
      (node (ref "IC9") (pin "15") (pinfunction "DVDD_15") (pintype "bidirectional"))
      (node (ref "IC9") (pin "16") (pinfunction "VP_16") (pintype "bidirectional"))
      (node (ref "L11") (pin "2") (pinfunction "2_2") (pintype "passive"))
    )
    (net (code "46") (name "Net-(IC9-REFIN)") (class "Default")
      (node (ref "C29") (pin "2") (pinfunction "2_2") (pintype "passive"))
      (node (ref "IC9") (pin "8") (pinfunction "REFIN_8") (pintype "bidirectional"))
    )
    (net (code "47") (name "Net-(IC9-RFINB)") (class "Default")
      (node (ref "IC9") (pin "5") (pinfunction "RFINB_5") (pintype "bidirectional"))
      (node (ref "R19") (pin "2") (pinfunction "2_2") (pintype "passive"))
    )
    (net (code "48") (name "Net-(IC9-RSET)") (class "Default")
      (node (ref "IC9") (pin "1") (pinfunction "RSET_1") (pintype "bidirectional"))
      (node (ref "R23") (pin "1") (pinfunction "1_1") (pintype "passive"))
    )
    (net (code "49") (name "Net-(IC9-SDVDD)") (class "Default")
      (node (ref "C34") (pin "2") (pinfunction "2_2") (pintype "passive"))
      (node (ref "C35") (pin "2") (pinfunction "2_2") (pintype "passive"))
      (node (ref "IC9") (pin "10") (pinfunction "SDVDD_10") (pintype "bidirectional"))
      (node (ref "L10") (pin "2") (pinfunction "2_2") (pintype "passive"))
    )
    (net (code "50") (name "Net-(IC10-+)") (class "Default")
      (node (ref "C45") (pin "1") (pinfunction "1_1") (pintype "passive"))
      (node (ref "C52") (pin "1") (pinfunction "1_1") (pintype "passive"))
      (node (ref "IC10") (pin "P$3") (pinfunction "+_P$3") (pintype "bidirectional"))
      (node (ref "R20") (pin "2") (pinfunction "2_2") (pintype "passive"))
      (node (ref "R21") (pin "2") (pinfunction "2_2") (pintype "passive"))
    )
    (net (code "51") (name "Net-(IC10-+VE)") (class "Default")
      (node (ref "C39") (pin "1") (pinfunction "1_1") (pintype "passive"))
      (node (ref "C40") (pin "1") (pinfunction "1_1") (pintype "passive"))
      (node (ref "IC10") (pin "P$6") (pinfunction "+VE_P$6") (pintype "bidirectional"))
      (node (ref "L9") (pin "1") (pinfunction "1_1") (pintype "passive"))
    )
    (net (code "52") (name "Net-(IC10--)") (class "Default")
      (node (ref "C46") (pin "2") (pinfunction "2_2") (pintype "passive"))
      (node (ref "C50") (pin "2") (pinfunction "2_2") (pintype "passive"))
      (node (ref "IC10") (pin "P$4") (pinfunction "-_P$4") (pintype "bidirectional"))
      (node (ref "R24") (pin "1") (pinfunction "1_1") (pintype "passive"))
      (node (ref "R25") (pin "1") (pinfunction "1_1") (pintype "passive"))
    )
    (net (code "53") (name "Net-(IC10-OP)") (class "Default")
      (node (ref "C43") (pin "2") (pinfunction "2_2") (pintype "passive"))
      (node (ref "IC10") (pin "P$1") (pinfunction "OP_P$1") (pintype "bidirectional"))
      (node (ref "R22") (pin "2") (pinfunction "2_2") (pintype "passive"))
    )
    (net (code "54") (name "Net-(IC11-CTRL)") (class "Default")
      (node (ref "IC11") (pin "S") (pinfunction "CTRL_S") (pintype "bidirectional"))
      (node (ref "R31") (pin "2") (pinfunction "2_2") (pintype "passive"))
      (node (ref "R32") (pin "1") (pinfunction "1_1") (pintype "passive"))
    )
    (net (code "55") (name "Net-(L7-Pad1)") (class "Default")
      (node (ref "L7") (pin "1") (pinfunction "1_1") (pintype "passive"))
      (node (ref "R17") (pin "2") (pinfunction "2_2") (pintype "passive"))
    )
    (net (code "56") (name "Net-(L12-Pad1)") (class "Default")
      (node (ref "L12") (pin "1") (pinfunction "1_1") (pintype "passive"))
      (node (ref "R24") (pin "2") (pinfunction "2_2") (pintype "passive"))
    )
    (net (code "57") (name "Net-(LED1-PadA)") (class "Default")
      (node (ref "LED1") (pin "A") (pinfunction "A_A") (pintype "passive"))
      (node (ref "R7") (pin "2") (pinfunction "2_2") (pintype "passive"))
    )
    (net (code "58") (name "Net-(LED2-PadA)") (class "Default")
      (node (ref "LED2") (pin "A") (pinfunction "A_A") (pintype "passive"))
      (node (ref "R8") (pin "2") (pinfunction "2_2") (pintype "passive"))
    )
    (net (code "59") (name "Net-(LED3-PadA)") (class "Default")
      (node (ref "LED3") (pin "A") (pinfunction "A_A") (pintype "passive"))
      (node (ref "R9") (pin "2") (pinfunction "2_2") (pintype "passive"))
    )
    (net (code "60") (name "Net-(OSC1-CTRL)") (class "Default")
      (node (ref "C24") (pin "1") (pinfunction "1_1") (pintype "passive"))
      (node (ref "C25") (pin "1") (pinfunction "1_1") (pintype "passive"))
      (node (ref "OSC1") (pin "REF") (pinfunction "CTRL_REF") (pintype "bidirectional"))
      (node (ref "R13") (pin "2") (pinfunction "2_2") (pintype "passive"))
      (node (ref "R14") (pin "2") (pinfunction "2_2") (pintype "passive"))
    )
    (net (code "61") (name "Net-(OSC2-CTRL)") (class "Default")
      (node (ref "C51") (pin "2") (pinfunction "2_2") (pintype "passive"))
      (node (ref "OSC2") (pin "P$2") (pinfunction "CTRL_P$2") (pintype "bidirectional"))
      (node (ref "R22") (pin "1") (pinfunction "1_1") (pintype "passive"))
    )
    (net (code "62") (name "Net-(OSC2-OP)") (class "Default")
      (node (ref "OSC2") (pin "P$10") (pinfunction "OP_P$10") (pintype "bidirectional"))
      (node (ref "R16") (pin "1") (pinfunction "1_1") (pintype "passive"))
      (node (ref "R18") (pin "1") (pinfunction "1_1") (pintype "passive"))
    )
    (net (code "63") (name "Net-(OSC2-VCC)") (class "Default")
      (node (ref "C32") (pin "1") (pinfunction "1_1") (pintype "passive"))
      (node (ref "C33") (pin "1") (pinfunction "1_1") (pintype "passive"))
      (node (ref "L6") (pin "1") (pinfunction "1_1") (pintype "passive"))
      (node (ref "OSC2") (pin "P$14") (pinfunction "VCC_P$14") (pintype "bidirectional"))
    )
    (net (code "64") (name "Net-(Q1-G)") (class "Default")
      (node (ref "C41") (pin "2") (pinfunction "2_2") (pintype "passive"))
      (node (ref "Q1") (pin "1") (pinfunction "G_1") (pintype "passive"))
    )
    (net (code "65") (name "Net-(Q1-S)") (class "Default")
      (node (ref "C38") (pin "1") (pinfunction "1_1") (pintype "passive"))
      (node (ref "Q1") (pin "3") (pinfunction "S_3") (pintype "passive"))
      (node (ref "R17") (pin "1") (pinfunction "1_1") (pintype "passive"))
    )
    (net (code "66") (name "Net-(TXFMR1-PRI_2)") (class "Default")
      (node (ref "SCK1") (pin "1") (pinfunction "1_1") (pintype "passive"))
      (node (ref "TXFMR1") (pin "3") (pinfunction "PRI_2_3") (pintype "bidirectional"))
    )
    (net (code "67") (name "Net-(TXFMR1-SEC_1)") (class "Default")
      (node (ref "L1") (pin "2") (pinfunction "2_2") (pintype "passive"))
      (node (ref "R3") (pin "1") (pinfunction "1_1") (pintype "passive"))
      (node (ref "TXFMR1") (pin "4") (pinfunction "SEC_1_4") (pintype "bidirectional"))
    )
    (net (code "68") (name "Net-(VR1-S)") (class "Default")
      (node (ref "R13") (pin "1") (pinfunction "1_1") (pintype "passive"))
      (node (ref "VR1") (pin "2") (pinfunction "S_2") (pintype "passive"))
    )
    (net (code "69") (name "PLL_RF_IN") (class "Default")
      (node (ref "C42") (pin "2") (pinfunction "2_2") (pintype "passive"))
      (node (ref "IC9") (pin "6") (pinfunction "RFINA_6") (pintype "bidirectional"))
    )
    (net (code "70") (name "SCK") (class "Default")
      (node (ref "IC4") (pin "11") (pinfunction "CLK_11") (pintype "bidirectional"))
      (node (ref "IC5") (pin "7") (pinfunction "PB2_(SCK/USCK/SCL/ADC1/T0/INT0/PCINT2)_7") (pintype "bidirectional"))
      (node (ref "IC9") (pin "11") (pinfunction "CLK_11") (pintype "bidirectional"))
      (node (ref "SV1") (pin "3") (pinfunction "3_3") (pintype "passive"))
    )
    (net (code "71") (name "unconnected-(D1-A1-Pad1)") (class "Default")
      (node (ref "D1") (pin "1") (pinfunction "A1_1") (pintype "passive"))
    )
    (net (code "72") (name "unconnected-(TXFMR1-NC-Pad2)") (class "Default")
      (node (ref "TXFMR1") (pin "2") (pinfunction "NC_2") (pintype "no_connect"))
    )
    (net (code "73") (name "unconnected-(TXFMR1-SEC_2-Pad5)") (class "Default")
      (node (ref "TXFMR1") (pin "5") (pinfunction "SEC_2_5") (pintype "bidirectional"))
    )
  )
)
